# mapleSDuino-V0_1_015-eagle7.net
KiCad netlist of a schematic drawn in EAGLE
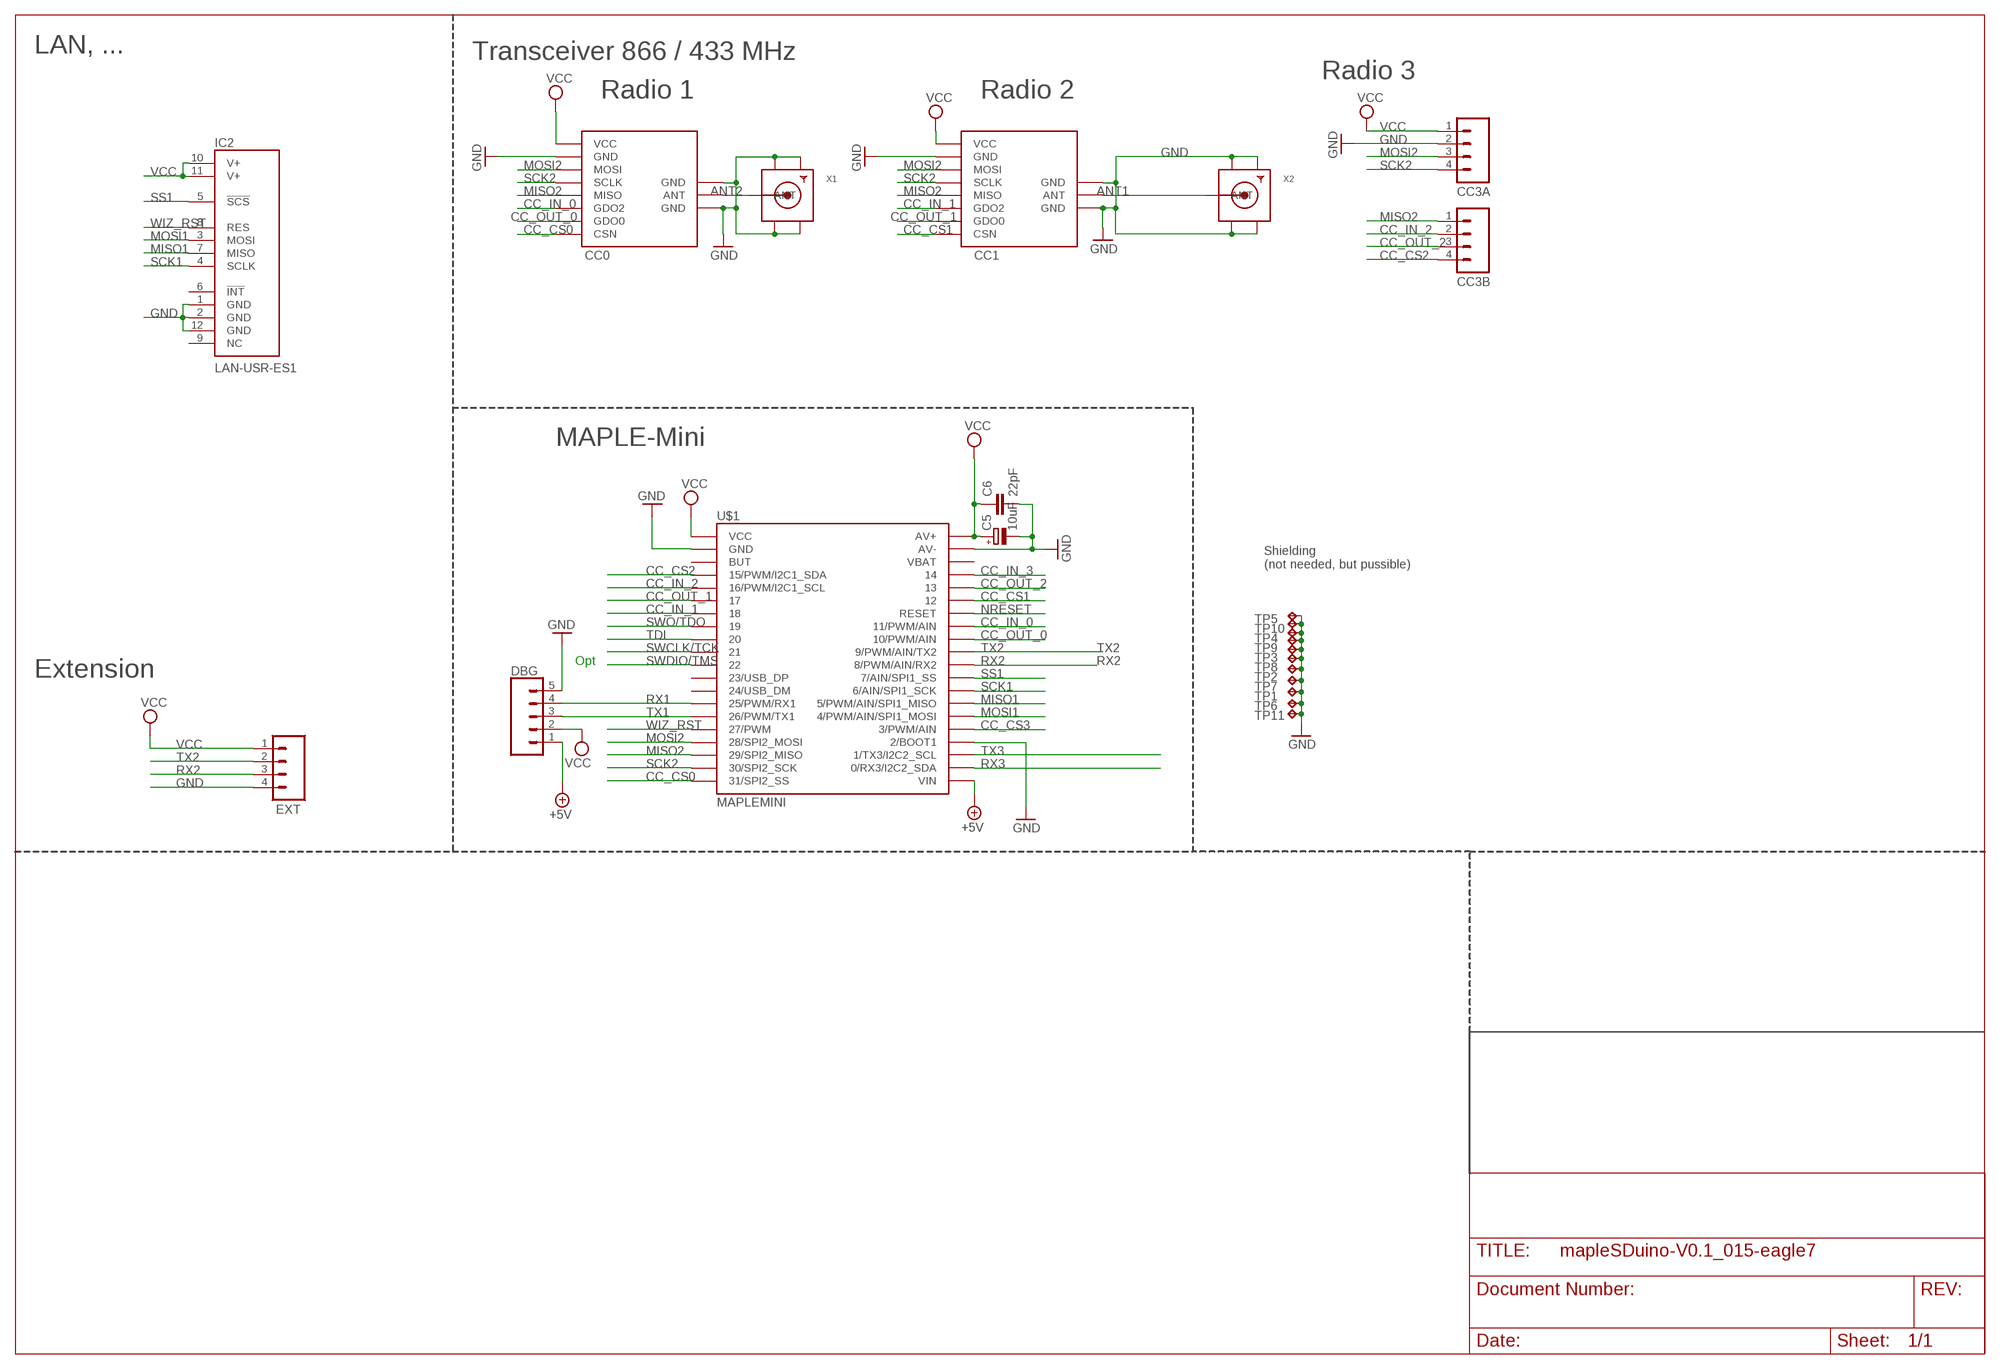
[diagram p0: schematic, sheet 1]

(export (version "E")
  (design (tool "Eeschema 10.0.6"))
  (components
    (comp (ref "C5")
      (value "10uF")
      (footprint "eagle-import:R_2012-12W")
      (libsource (lib "eagle-import") (part "CPOL-EUR/2012-12W"))
    )
    (comp (ref "C6")
      (value "22pF")
      (footprint "eagle-import:C0805")
      (libsource (lib "eagle-import") (part "C-EUC0805"))
    )
    (comp (ref "CC0")
      (value "CC1101")
      (footprint "eagle-import:CC1101_MODULE1_SMD")
      (libsource (lib "eagle-import") (part "CC1101_MODULE1SMD"))
    )
    (comp (ref "CC1")
      (value "CC1101_MODULE1SMD")
      (footprint "eagle-import:CC1101_MODULE1_SMD")
      (libsource (lib "eagle-import") (part "CC1101_MODULE1SMD"))
    )
    (comp (ref "CC3A")
      (value "CONN_04PTH")
      (footprint "eagle-import:1X04")
      (libsource (lib "eagle-import") (part "CONN_04PTH"))
    )
    (comp (ref "CC3B")
      (value "CONN_04PTH")
      (footprint "eagle-import:1X04")
      (libsource (lib "eagle-import") (part "CONN_04PTH"))
    )
    (comp (ref "DBG")
      (value "CONN_05LOCK")
      (footprint "eagle-import:1X05_LOCK")
      (libsource (lib "eagle-import") (part "CONN_05LOCK"))
    )
    (comp (ref "EXT")
      (value "CONN_04PTH")
      (footprint "eagle-import:1X04")
      (libsource (lib "eagle-import") (part "CONN_04PTH"))
    )
    (comp (ref "IC2")
      (value "LAN-USR-ES1")
      (footprint "eagle-import:USR-ES1")
      (libsource (lib "eagle-import") (part "LAN-USR-ES1"))
    )
    (comp (ref "TP1")
      (value "TPTP06SQ")
      (footprint "eagle-import:TP06SQ")
      (libsource (lib "eagle-import") (part "TPTP06SQ"))
    )
    (comp (ref "TP2")
      (value "TPTP06SQ")
      (footprint "eagle-import:TP06SQ")
      (libsource (lib "eagle-import") (part "TPTP06SQ"))
    )
    (comp (ref "TP3")
      (value "TPTP06SQ")
      (footprint "eagle-import:TP06SQ")
      (libsource (lib "eagle-import") (part "TPTP06SQ"))
    )
    (comp (ref "TP4")
      (value "TPTP06SQ")
      (footprint "eagle-import:TP06SQ")
      (libsource (lib "eagle-import") (part "TPTP06SQ"))
    )
    (comp (ref "TP5")
      (value "TPTP06SQ")
      (footprint "eagle-import:TP06SQ")
      (libsource (lib "eagle-import") (part "TPTP06SQ"))
    )
    (comp (ref "TP6")
      (value "TPTP06SQ")
      (footprint "eagle-import:TP06SQ")
      (libsource (lib "eagle-import") (part "TPTP06SQ"))
    )
    (comp (ref "TP7")
      (value "TPTP06SQ")
      (footprint "eagle-import:TP06SQ")
      (libsource (lib "eagle-import") (part "TPTP06SQ"))
    )
    (comp (ref "TP8")
      (value "TPTP06SQ")
      (footprint "eagle-import:TP06SQ")
      (libsource (lib "eagle-import") (part "TPTP06SQ"))
    )
    (comp (ref "TP9")
      (value "TPTP06SQ")
      (footprint "eagle-import:TP06SQ")
      (libsource (lib "eagle-import") (part "TPTP06SQ"))
    )
    (comp (ref "TP10")
      (value "TPTP06SQ")
      (footprint "eagle-import:TP06SQ")
      (libsource (lib "eagle-import") (part "TPTP06SQ"))
    )
    (comp (ref "TP11")
      (value "TPTP06SQ")
      (footprint "eagle-import:TP06SQ")
      (libsource (lib "eagle-import") (part "TPTP06SQ"))
    )
    (comp (ref "U$1")
      (value "MAPLEMINI")
      (footprint "eagle-import:20-DIP")
      (libsource (lib "eagle-import") (part "MAPLEMINI"))
    )
    (comp (ref "X1")
      (value "SMACONNECTOR_EDGE")
      (footprint "eagle-import:SMA_EDGELAUNCH")
      (libsource (lib "eagle-import") (part "SMACONNECTOR_EDGE"))
    )
    (comp (ref "X2")
      (value "SMACONNECTOR_EDGE")
      (footprint "eagle-import:SMA_EDGELAUNCH")
      (libsource (lib "eagle-import") (part "SMACONNECTOR_EDGE"))
    )
  )
  (nets
    (net (code "1") (name "+5V") (class "Default")
      (node (ref "DBG") (pin "1") (pinfunction "1_1") (pintype "passive"))
      (node (ref "U$1") (pin "21") (pinfunction "VIN_21") (pintype "bidirectional"))
    )
    (net (code "2") (name "/ANT1") (class "Default")
      (node (ref "CC1") (pin "ANT") (pinfunction "ANT_ANT") (pintype "output"))
      (node (ref "X2") (pin "P") (pinfunction "ANT_P") (pintype "bidirectional"))
    )
    (net (code "3") (name "/ANT2") (class "Default")
      (node (ref "CC0") (pin "ANT") (pinfunction "ANT_ANT") (pintype "output"))
      (node (ref "X1") (pin "P") (pinfunction "ANT_P") (pintype "bidirectional"))
    )
    (net (code "4") (name "/CC_CS0") (class "Default")
      (node (ref "CC0") (pin "CSN") (pinfunction "CSN_CSN") (pintype "bidirectional"))
      (node (ref "U$1") (pin "20") (pinfunction "31/SPI2_SS_20") (pintype "bidirectional"))
    )
    (net (code "5") (name "/CC_CS1") (class "Default")
      (node (ref "CC1") (pin "CSN") (pinfunction "CSN_CSN") (pintype "bidirectional"))
      (node (ref "U$1") (pin "35") (pinfunction "12_35") (pintype "bidirectional"))
    )
    (net (code "6") (name "/CC_CS2") (class "Default")
      (node (ref "CC3B") (pin "4") (pinfunction "4_4") (pintype "passive"))
      (node (ref "U$1") (pin "4") (pinfunction "15/PWM/I2C1_SDA_4") (pintype "bidirectional"))
    )
    (net (code "7") (name "/CC_CS3") (class "Default")
      (node (ref "U$1") (pin "25") (pinfunction "3/PWM/AIN_25") (pintype "bidirectional"))
    )
    (net (code "8") (name "/CC_IN_0") (class "Default")
      (node (ref "CC0") (pin "GDO2") (pinfunction "GDO2_GDO2") (pintype "bidirectional"))
      (node (ref "U$1") (pin "33") (pinfunction "11/PWM/AIN_33") (pintype "bidirectional"))
    )
    (net (code "9") (name "/CC_IN_1") (class "Default")
      (node (ref "CC1") (pin "GDO2") (pinfunction "GDO2_GDO2") (pintype "bidirectional"))
      (node (ref "U$1") (pin "7") (pinfunction "18_7") (pintype "bidirectional"))
    )
    (net (code "10") (name "/CC_IN_2") (class "Default")
      (node (ref "CC3B") (pin "2") (pinfunction "2_2") (pintype "passive"))
      (node (ref "U$1") (pin "5") (pinfunction "16/PWM/I2C1_SCL_5") (pintype "bidirectional"))
    )
    (net (code "11") (name "/CC_IN_3") (class "Default")
      (node (ref "U$1") (pin "37") (pinfunction "14_37") (pintype "bidirectional"))
    )
    (net (code "12") (name "/CC_OUT_0") (class "Default")
      (node (ref "CC0") (pin "GDO0") (pinfunction "GDO0_GDO0") (pintype "bidirectional"))
      (node (ref "U$1") (pin "32") (pinfunction "10/PWM/AIN_32") (pintype "bidirectional"))
    )
    (net (code "13") (name "/CC_OUT_1") (class "Default")
      (node (ref "CC1") (pin "GDO0") (pinfunction "GDO0_GDO0") (pintype "bidirectional"))
      (node (ref "U$1") (pin "6") (pinfunction "17_6") (pintype "bidirectional"))
    )
    (net (code "14") (name "/CC_OUT_2") (class "Default")
      (node (ref "CC3B") (pin "3") (pinfunction "3_3") (pintype "passive"))
      (node (ref "U$1") (pin "36") (pinfunction "13_36") (pintype "bidirectional"))
    )
    (net (code "15") (name "/MISO1") (class "Default")
      (node (ref "IC2") (pin "7") (pinfunction "MISO_7") (pintype "bidirectional"))
      (node (ref "U$1") (pin "27") (pinfunction "5/PWM/AIN/SPI1_MISO_27") (pintype "bidirectional"))
    )
    (net (code "16") (name "/MISO2") (class "Default")
      (node (ref "CC0") (pin "MISO") (pinfunction "MISO_MISO") (pintype "bidirectional"))
      (node (ref "CC1") (pin "MISO") (pinfunction "MISO_MISO") (pintype "bidirectional"))
      (node (ref "CC3B") (pin "1") (pinfunction "1_1") (pintype "passive"))
      (node (ref "U$1") (pin "18") (pinfunction "29/SPI2_MISO_18") (pintype "bidirectional"))
    )
    (net (code "17") (name "/MOSI1") (class "Default")
      (node (ref "IC2") (pin "3") (pinfunction "MOSI_3") (pintype "bidirectional"))
      (node (ref "U$1") (pin "26") (pinfunction "4/PWM/AIN/SPI1_MOSI_26") (pintype "bidirectional"))
    )
    (net (code "18") (name "/MOSI2") (class "Default")
      (node (ref "CC0") (pin "MOSI") (pinfunction "MOSI_MOSI") (pintype "bidirectional"))
      (node (ref "CC1") (pin "MOSI") (pinfunction "MOSI_MOSI") (pintype "bidirectional"))
      (node (ref "CC3A") (pin "3") (pinfunction "3_3") (pintype "passive"))
      (node (ref "U$1") (pin "17") (pinfunction "28/SPI2_MOSI_17") (pintype "bidirectional"))
    )
    (net (code "19") (name "/NRESET") (class "Default")
      (node (ref "U$1") (pin "34") (pinfunction "RESET_34") (pintype "bidirectional"))
    )
    (net (code "20") (name "/RX1") (class "Default")
      (node (ref "DBG") (pin "4") (pinfunction "4_4") (pintype "passive"))
      (node (ref "U$1") (pin "14") (pinfunction "25/PWM/RX1_14") (pintype "bidirectional"))
    )
    (net (code "21") (name "/RX2") (class "Default")
      (node (ref "EXT") (pin "3") (pinfunction "3_3") (pintype "passive"))
      (node (ref "U$1") (pin "30") (pinfunction "8/PWM/AIN/RX2_30") (pintype "bidirectional"))
    )
    (net (code "22") (name "/RX3") (class "Default")
      (node (ref "U$1") (pin "22") (pinfunction "0/RX3/I2C2_SDA_22") (pintype "bidirectional"))
    )
    (net (code "23") (name "/SCK1") (class "Default")
      (node (ref "IC2") (pin "4") (pinfunction "SCLK_4") (pintype "input"))
      (node (ref "U$1") (pin "28") (pinfunction "6/AIN/SPI1_SCK_28") (pintype "bidirectional"))
    )
    (net (code "24") (name "/SCK2") (class "Default")
      (node (ref "CC0") (pin "SCLK") (pinfunction "SCLK_SCLK") (pintype "bidirectional"))
      (node (ref "CC1") (pin "SCLK") (pinfunction "SCLK_SCLK") (pintype "bidirectional"))
      (node (ref "CC3A") (pin "4") (pinfunction "4_4") (pintype "passive"))
      (node (ref "U$1") (pin "19") (pinfunction "30/SPI2_SCK_19") (pintype "bidirectional"))
    )
    (net (code "25") (name "/SS1") (class "Default")
      (node (ref "IC2") (pin "5") (pinfunction "~{SCS}_5") (pintype "input"))
      (node (ref "U$1") (pin "29") (pinfunction "7/AIN/SPI1_SS_29") (pintype "bidirectional"))
    )
    (net (code "26") (name "/SWCLK{slash}TCK") (class "Default")
      (node (ref "U$1") (pin "10") (pinfunction "21_10") (pintype "bidirectional"))
    )
    (net (code "27") (name "/SWDIO{slash}TMS") (class "Default")
      (node (ref "U$1") (pin "11") (pinfunction "22_11") (pintype "bidirectional"))
    )
    (net (code "28") (name "/SWO{slash}TDO") (class "Default")
      (node (ref "U$1") (pin "8") (pinfunction "19_8") (pintype "bidirectional"))
    )
    (net (code "29") (name "/TDI") (class "Default")
      (node (ref "U$1") (pin "9") (pinfunction "20_9") (pintype "bidirectional"))
    )
    (net (code "30") (name "/TX1") (class "Default")
      (node (ref "DBG") (pin "3") (pinfunction "3_3") (pintype "passive"))
      (node (ref "U$1") (pin "15") (pinfunction "26/PWM/TX1_15") (pintype "bidirectional"))
    )
    (net (code "31") (name "/TX2") (class "Default")
      (node (ref "EXT") (pin "2") (pinfunction "2_2") (pintype "passive"))
      (node (ref "U$1") (pin "31") (pinfunction "9/PWM/AIN/TX2_31") (pintype "bidirectional"))
    )
    (net (code "32") (name "/TX3") (class "Default")
      (node (ref "U$1") (pin "23") (pinfunction "1/TX3/I2C2_SCL_23") (pintype "bidirectional"))
    )
    (net (code "33") (name "/WIZ_RST") (class "Default")
      (node (ref "IC2") (pin "8") (pinfunction "RES_8") (pintype "input"))
      (node (ref "U$1") (pin "16") (pinfunction "27/PWM_16") (pintype "bidirectional"))
    )
    (net (code "34") (name "GND") (class "Default")
      (node (ref "C5") (pin "-") (pinfunction "-_-") (pintype "passive"))
      (node (ref "C6") (pin "2") (pinfunction "2_2") (pintype "passive"))
      (node (ref "CC0") (pin "GND@0") (pinfunction "GND_GND@0") (pintype "power_in"))
      (node (ref "CC0") (pin "GND@1") (pinfunction "GND_GND@1") (pintype "power_in"))
      (node (ref "CC0") (pin "GND@2") (pinfunction "GND_GND@2") (pintype "power_in"))
      (node (ref "CC1") (pin "GND@0") (pinfunction "GND_GND@0") (pintype "power_in"))
      (node (ref "CC1") (pin "GND@1") (pinfunction "GND_GND@1") (pintype "power_in"))
      (node (ref "CC1") (pin "GND@2") (pinfunction "GND_GND@2") (pintype "power_in"))
      (node (ref "CC3A") (pin "2") (pinfunction "2_2") (pintype "passive"))
      (node (ref "DBG") (pin "5") (pinfunction "5_5") (pintype "passive"))
      (node (ref "EXT") (pin "4") (pinfunction "4_4") (pintype "passive"))
      (node (ref "IC2") (pin "1") (pinfunction "GND_1") (pintype "power_in"))
      (node (ref "IC2") (pin "12") (pinfunction "GND_12") (pintype "power_in"))
      (node (ref "IC2") (pin "2") (pinfunction "GND_2") (pintype "power_in"))
      (node (ref "TP1") (pin "TP") (pinfunction "TP_TP") (pintype "input"))
      (node (ref "TP10") (pin "TP") (pinfunction "TP_TP") (pintype "input"))
      (node (ref "TP11") (pin "TP") (pinfunction "TP_TP") (pintype "input"))
      (node (ref "TP2") (pin "TP") (pinfunction "TP_TP") (pintype "input"))
      (node (ref "TP3") (pin "TP") (pinfunction "TP_TP") (pintype "input"))
      (node (ref "TP4") (pin "TP") (pinfunction "TP_TP") (pintype "input"))
      (node (ref "TP5") (pin "TP") (pinfunction "TP_TP") (pintype "input"))
      (node (ref "TP6") (pin "TP") (pinfunction "TP_TP") (pintype "input"))
      (node (ref "TP7") (pin "TP") (pinfunction "TP_TP") (pintype "input"))
      (node (ref "TP8") (pin "TP") (pinfunction "TP_TP") (pintype "input"))
      (node (ref "TP9") (pin "TP") (pinfunction "TP_TP") (pintype "input"))
      (node (ref "U$1") (pin "2") (pinfunction "GND_2") (pintype "bidirectional"))
      (node (ref "U$1") (pin "24") (pinfunction "2/BOOT1_24") (pintype "bidirectional"))
      (node (ref "U$1") (pin "39") (pinfunction "AV-_39") (pintype "bidirectional"))
      (node (ref "X1") (pin "GND@1") (pinfunction "GND4_GND@1") (pintype "power_in"))
      (node (ref "X1") (pin "GND@2") (pinfunction "GND3_GND@2") (pintype "power_in"))
      (node (ref "X1") (pin "GND@3") (pinfunction "GND2_GND@3") (pintype "power_in"))
      (node (ref "X1") (pin "GND@4") (pinfunction "GND1_GND@4") (pintype "power_in"))
      (node (ref "X2") (pin "GND@1") (pinfunction "GND4_GND@1") (pintype "power_in"))
      (node (ref "X2") (pin "GND@2") (pinfunction "GND3_GND@2") (pintype "power_in"))
      (node (ref "X2") (pin "GND@3") (pinfunction "GND2_GND@3") (pintype "power_in"))
      (node (ref "X2") (pin "GND@4") (pinfunction "GND1_GND@4") (pintype "power_in"))
    )
    (net (code "35") (name "VCC") (class "Default")
      (node (ref "C5") (pin "+") (pinfunction "+_+") (pintype "passive"))
      (node (ref "C6") (pin "1") (pinfunction "1_1") (pintype "passive"))
      (node (ref "CC0") (pin "VCC") (pinfunction "VCC_VCC") (pintype "power_in"))
      (node (ref "CC1") (pin "VCC") (pinfunction "VCC_VCC") (pintype "power_in"))
      (node (ref "CC3A") (pin "1") (pinfunction "1_1") (pintype "passive"))
      (node (ref "DBG") (pin "2") (pinfunction "2_2") (pintype "passive"))
      (node (ref "EXT") (pin "1") (pinfunction "1_1") (pintype "passive"))
      (node (ref "IC2") (pin "10") (pinfunction "V+_10") (pintype "power_in"))
      (node (ref "IC2") (pin "11") (pinfunction "V+_11") (pintype "power_in"))
      (node (ref "U$1") (pin "1") (pinfunction "VCC_1") (pintype "bidirectional"))
      (node (ref "U$1") (pin "40") (pinfunction "AV+_40") (pintype "bidirectional"))
    )
    (net (code "36") (name "unconnected-(IC2-NC-Pad9)") (class "Default")
      (node (ref "IC2") (pin "9") (pinfunction "NC_9") (pintype "no_connect"))
    )
    (net (code "37") (name "unconnected-(IC2-~{INT}-Pad6)") (class "Default")
      (node (ref "IC2") (pin "6") (pinfunction "~{INT}_6") (pintype "output"))
    )
    (net (code "38") (name "unconnected-(U$1-23{slash}USB_DP-Pad12)") (class "Default")
      (node (ref "U$1") (pin "12") (pinfunction "23/USB_DP_12") (pintype "bidirectional"))
    )
    (net (code "39") (name "unconnected-(U$1-24{slash}USB_DM-Pad13)") (class "Default")
      (node (ref "U$1") (pin "13") (pinfunction "24/USB_DM_13") (pintype "bidirectional"))
    )
    (net (code "40") (name "unconnected-(U$1-BUT-Pad3)") (class "Default")
      (node (ref "U$1") (pin "3") (pinfunction "BUT_3") (pintype "bidirectional"))
    )
    (net (code "41") (name "unconnected-(U$1-VBAT-Pad38)") (class "Default")
      (node (ref "U$1") (pin "38") (pinfunction "VBAT_38") (pintype "bidirectional"))
    )
  )
)
